# PILockbox_Zak_Jan_2016.net
KiCad netlist of a schematic drawn in EAGLE
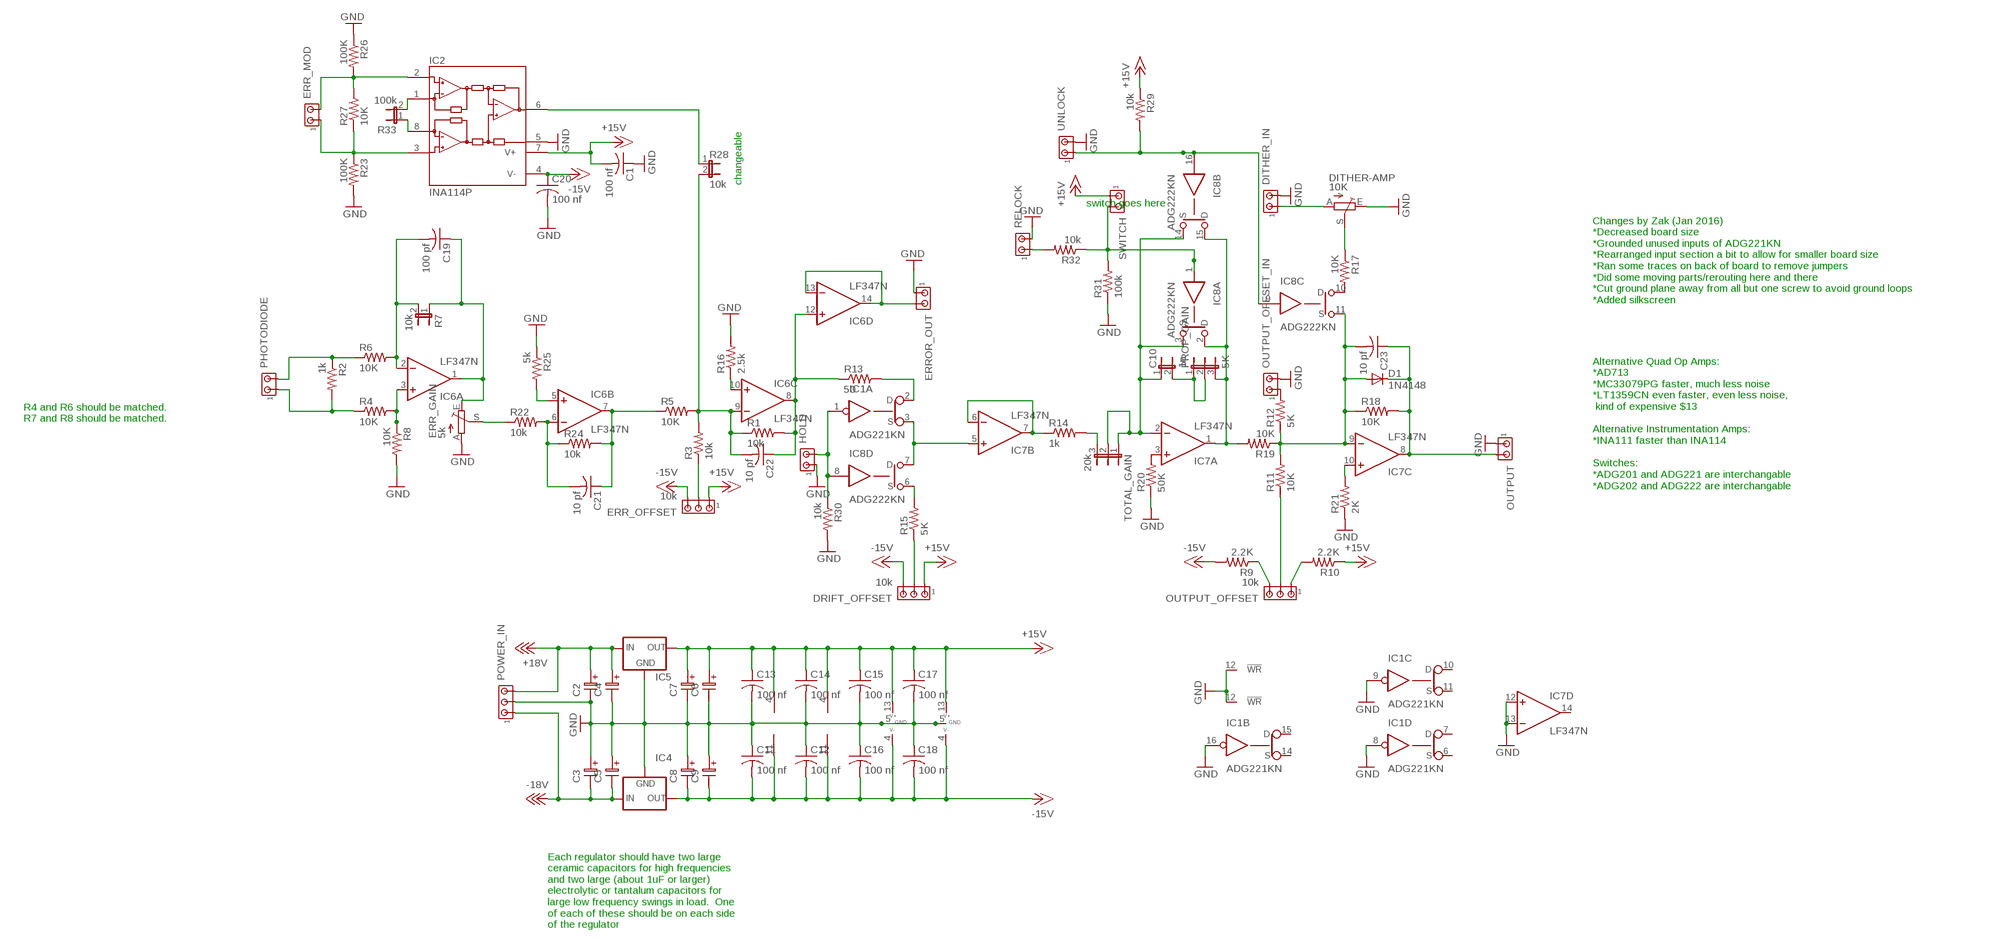
[diagram p0: schematic, sheet 1]

(export (version "E")
  (design (tool "Eeschema 10.0.6"))
  (components
    (comp (ref "C1")
      (value "100 nf")
      (footprint "eagle-import:C0805")
      (libsource (lib "eagle-import") (part "C-USC0805"))
    )
    (comp (ref "C2")
      (value "ELC-2,5")
      (footprint "eagle-import:ES-2,5")
      (libsource (lib "eagle-import") (part "ELC-2,5"))
    )
    (comp (ref "C3")
      (value "ELC-2,5")
      (footprint "eagle-import:ES-2,5")
      (libsource (lib "eagle-import") (part "ELC-2,5"))
    )
    (comp (ref "C4")
      (value "ELC-2,5")
      (footprint "eagle-import:ES-2,5")
      (libsource (lib "eagle-import") (part "ELC-2,5"))
    )
    (comp (ref "C5")
      (value "ELC-2,5")
      (footprint "eagle-import:ES-2,5")
      (libsource (lib "eagle-import") (part "ELC-2,5"))
    )
    (comp (ref "C6")
      (value "ELC-2,5")
      (footprint "eagle-import:ES-2,5")
      (libsource (lib "eagle-import") (part "ELC-2,5"))
    )
    (comp (ref "C7")
      (value "ELC-2,5")
      (footprint "eagle-import:ES-2,5")
      (libsource (lib "eagle-import") (part "ELC-2,5"))
    )
    (comp (ref "C8")
      (value "ELC-2,5")
      (footprint "eagle-import:ES-2,5")
      (libsource (lib "eagle-import") (part "ELC-2,5"))
    )
    (comp (ref "C9")
      (value "ELC-2,5")
      (footprint "eagle-import:ES-2,5")
      (libsource (lib "eagle-import") (part "ELC-2,5"))
    )
    (comp (ref "C10")
      (value "1n")
      (footprint "eagle-import:JP1")
      (libsource (lib "eagle-import") (part "JP1E"))
    )
    (comp (ref "C11")
      (value "100 nf")
      (footprint "eagle-import:C0805")
      (libsource (lib "eagle-import") (part "C-USC0805"))
    )
    (comp (ref "C12")
      (value "100 nf")
      (footprint "eagle-import:C0805")
      (libsource (lib "eagle-import") (part "C-USC0805"))
    )
    (comp (ref "C13")
      (value "100 nf")
      (footprint "eagle-import:C0805")
      (libsource (lib "eagle-import") (part "C-USC0805"))
    )
    (comp (ref "C14")
      (value "100 nf")
      (footprint "eagle-import:C0805")
      (libsource (lib "eagle-import") (part "C-USC0805"))
    )
    (comp (ref "C15")
      (value "100 nf")
      (footprint "eagle-import:C0805")
      (libsource (lib "eagle-import") (part "C-USC0805"))
    )
    (comp (ref "C16")
      (value "100 nf")
      (footprint "eagle-import:C0805")
      (libsource (lib "eagle-import") (part "C-USC0805"))
    )
    (comp (ref "C17")
      (value "100 nf")
      (footprint "eagle-import:C0805")
      (libsource (lib "eagle-import") (part "C-USC0805"))
    )
    (comp (ref "C18")
      (value "100 nf")
      (footprint "eagle-import:C0805")
      (libsource (lib "eagle-import") (part "C-USC0805"))
    )
    (comp (ref "C19")
      (value "100 pf")
      (footprint "eagle-import:C0805")
      (libsource (lib "eagle-import") (part "C-USC0805"))
    )
    (comp (ref "C20")
      (value "100 nf")
      (footprint "eagle-import:C0805")
      (libsource (lib "eagle-import") (part "C-USC0805"))
    )
    (comp (ref "C21")
      (value "10 pf")
      (footprint "eagle-import:C0805")
      (libsource (lib "eagle-import") (part "C-USC0805"))
    )
    (comp (ref "C22")
      (value "10 pf")
      (footprint "eagle-import:C0805")
      (libsource (lib "eagle-import") (part "C-USC0805"))
    )
    (comp (ref "C23")
      (value "10 pf")
      (footprint "eagle-import:C0805")
      (libsource (lib "eagle-import") (part "C-USC0805"))
    )
    (comp (ref "D1")
      (value "1N4148")
      (footprint "eagle-import:DO35-10")
      (libsource (lib "eagle-import") (part "1N4148"))
    )
    (comp (ref "DITHER-AMP")
      (value "10K")
      (footprint "eagle-import:RJ9W")
      (libsource (lib "eagle-import") (part "TRIM_EU-RJ9W"))
    )
    (comp (ref "DITHER_IN")
      (value "MTA02-100")
      (footprint "eagle-import:10X02MTA")
      (libsource (lib "eagle-import") (part "MTA02-100"))
    )
    (comp (ref "DRIFT_OFFSET")
      (value "10k")
      (footprint "eagle-import:10X03MTA")
      (libsource (lib "eagle-import") (part "MTA03-100"))
    )
    (comp (ref "ERROR_OUT")
      (value "MTA02-100")
      (footprint "eagle-import:10X02MTA")
      (libsource (lib "eagle-import") (part "MTA02-100"))
    )
    (comp (ref "ERR_GAIN")
      (value "5k")
      (footprint "eagle-import:RJ9W")
      (libsource (lib "eagle-import") (part "TRIM_EU-RJ9W"))
    )
    (comp (ref "ERR_MOD")
      (value "MTA02-100")
      (footprint "eagle-import:10X02MTA")
      (libsource (lib "eagle-import") (part "MTA02-100"))
    )
    (comp (ref "ERR_OFFSET")
      (value "10k")
      (footprint "eagle-import:10X03MTA")
      (libsource (lib "eagle-import") (part "MTA03-100"))
    )
    (comp (ref "HOLD")
      (value "MTA02-100")
      (footprint "eagle-import:10X02MTA")
      (libsource (lib "eagle-import") (part "MTA02-100"))
    )
    (comp (ref "IC1")
      (value "ADG221KN")
      (footprint "eagle-import:DIL16")
      (libsource (lib "eagle-import") (part "ADG221KN"))
    )
    (comp (ref "IC2")
      (value "INA114P")
      (footprint "eagle-import:DIL08")
      (libsource (lib "eagle-import") (part "INA114P"))
    )
    (comp (ref "IC4")
      (value "79XXL")
      (footprint "eagle-import:79XXL")
      (libsource (lib "eagle-import") (part "79XXL"))
    )
    (comp (ref "IC5")
      (value "78XXL")
      (footprint "eagle-import:78XXL")
      (libsource (lib "eagle-import") (part "78XXL"))
    )
    (comp (ref "IC6")
      (value "LF347N")
      (footprint "eagle-import:DIL14")
      (libsource (lib "eagle-import") (part "LF347N"))
    )
    (comp (ref "IC7")
      (value "LF347N")
      (footprint "eagle-import:DIL14")
      (libsource (lib "eagle-import") (part "LF347N"))
    )
    (comp (ref "IC8")
      (value "ADG222KN")
      (footprint "eagle-import:DIL16")
      (libsource (lib "eagle-import") (part "ADG222KN"))
    )
    (comp (ref "OUTPUT")
      (value "MTA02-100")
      (footprint "eagle-import:10X02MTA")
      (libsource (lib "eagle-import") (part "MTA02-100"))
    )
    (comp (ref "OUTPUT_OFFSET")
      (value "10k")
      (footprint "eagle-import:10X03MTA")
      (libsource (lib "eagle-import") (part "MTA03-100"))
    )
    (comp (ref "OUTPUT_OFFSET_IN")
      (value "MTA02-100")
      (footprint "eagle-import:10X02MTA")
      (libsource (lib "eagle-import") (part "MTA02-100"))
    )
    (comp (ref "PHOTODIODE")
      (value "MTA02-100")
      (footprint "eagle-import:10X02MTA")
      (libsource (lib "eagle-import") (part "MTA02-100"))
    )
    (comp (ref "POWER_IN")
      (value "MTA03-100")
      (footprint "eagle-import:10X03MTA")
      (libsource (lib "eagle-import") (part "MTA03-100"))
    )
    (comp (ref "PROP_GAIN")
      (value "5K")
      (footprint "eagle-import:JP2")
      (libsource (lib "eagle-import") (part "JP2E"))
    )
    (comp (ref "R1")
      (value "10k")
      (footprint "eagle-import:R1206")
      (libsource (lib "eagle-import") (part "R-US_R1206"))
    )
    (comp (ref "R2")
      (value "1k")
      (footprint "eagle-import:R1206")
      (libsource (lib "eagle-import") (part "R-US_R1206"))
    )
    (comp (ref "R3")
      (value "10k")
      (footprint "eagle-import:R1206")
      (libsource (lib "eagle-import") (part "R-US_R1206"))
    )
    (comp (ref "R4")
      (value "10K")
      (footprint "eagle-import:R1206")
      (libsource (lib "eagle-import") (part "R-US_R1206"))
    )
    (comp (ref "R5")
      (value "10K")
      (footprint "eagle-import:R1206")
      (libsource (lib "eagle-import") (part "R-US_R1206"))
    )
    (comp (ref "R6")
      (value "10K")
      (footprint "eagle-import:R1206")
      (libsource (lib "eagle-import") (part "R-US_R1206"))
    )
    (comp (ref "R7")
      (value "10k")
      (footprint "eagle-import:JP1")
      (libsource (lib "eagle-import") (part "JP1E"))
    )
    (comp (ref "R8")
      (value "10K")
      (footprint "eagle-import:R1206")
      (libsource (lib "eagle-import") (part "R-US_R1206"))
    )
    (comp (ref "R9")
      (value "2.2K")
      (footprint "eagle-import:R1206")
      (libsource (lib "eagle-import") (part "R-US_R1206"))
    )
    (comp (ref "R10")
      (value "2.2K")
      (footprint "eagle-import:R1206")
      (libsource (lib "eagle-import") (part "R-US_R1206"))
    )
    (comp (ref "R11")
      (value "10K")
      (footprint "eagle-import:R1206")
      (libsource (lib "eagle-import") (part "R-US_R1206"))
    )
    (comp (ref "R12")
      (value "5K")
      (footprint "eagle-import:R1206")
      (libsource (lib "eagle-import") (part "R-US_R1206"))
    )
    (comp (ref "R13")
      (value "50")
      (footprint "eagle-import:R1206")
      (libsource (lib "eagle-import") (part "R-US_R1206"))
    )
    (comp (ref "R14")
      (value "1k")
      (footprint "eagle-import:R1206")
      (libsource (lib "eagle-import") (part "R-US_R1206"))
    )
    (comp (ref "R15")
      (value "5K")
      (footprint "eagle-import:R1206")
      (libsource (lib "eagle-import") (part "R-US_R1206"))
    )
    (comp (ref "R16")
      (value "2.5k")
      (footprint "eagle-import:R1206")
      (libsource (lib "eagle-import") (part "R-US_R1206"))
    )
    (comp (ref "R17")
      (value "10K")
      (footprint "eagle-import:R1206")
      (libsource (lib "eagle-import") (part "R-US_R1206"))
    )
    (comp (ref "R18")
      (value "10K")
      (footprint "eagle-import:R1206")
      (libsource (lib "eagle-import") (part "R-US_R1206"))
    )
    (comp (ref "R19")
      (value "10K")
      (footprint "eagle-import:R1206")
      (libsource (lib "eagle-import") (part "R-US_R1206"))
    )
    (comp (ref "R20")
      (value "50K")
      (footprint "eagle-import:R1206")
      (libsource (lib "eagle-import") (part "R-US_R1206"))
    )
    (comp (ref "R21")
      (value "2K")
      (footprint "eagle-import:R1206")
      (libsource (lib "eagle-import") (part "R-US_R1206"))
    )
    (comp (ref "R22")
      (value "10k")
      (footprint "eagle-import:R1206")
      (libsource (lib "eagle-import") (part "R-US_R1206"))
    )
    (comp (ref "R23")
      (value "100K")
      (footprint "eagle-import:R1206")
      (libsource (lib "eagle-import") (part "R-US_R1206"))
    )
    (comp (ref "R24")
      (value "10k")
      (footprint "eagle-import:R1206")
      (libsource (lib "eagle-import") (part "R-US_R1206"))
    )
    (comp (ref "R25")
      (value "5k")
      (footprint "eagle-import:R1206")
      (libsource (lib "eagle-import") (part "R-US_R1206"))
    )
    (comp (ref "R26")
      (value "100K")
      (footprint "eagle-import:R1206")
      (libsource (lib "eagle-import") (part "R-US_R1206"))
    )
    (comp (ref "R27")
      (value "10K")
      (footprint "eagle-import:R1206")
      (libsource (lib "eagle-import") (part "R-US_R1206"))
    )
    (comp (ref "R28")
      (value "10k")
      (footprint "eagle-import:JP1")
      (libsource (lib "eagle-import") (part "JP1E"))
    )
    (comp (ref "R29")
      (value "10k")
      (footprint "eagle-import:R1206")
      (libsource (lib "eagle-import") (part "R-US_R1206"))
    )
    (comp (ref "R30")
      (value "10k")
      (footprint "eagle-import:R1206")
      (libsource (lib "eagle-import") (part "R-US_R1206"))
    )
    (comp (ref "R31")
      (value "100k")
      (footprint "eagle-import:R1206")
      (libsource (lib "eagle-import") (part "R-US_R1206"))
    )
    (comp (ref "R32")
      (value "10k")
      (footprint "eagle-import:R1206")
      (libsource (lib "eagle-import") (part "R-US_R1206"))
    )
    (comp (ref "R33")
      (value "100k")
      (footprint "eagle-import:JP1")
      (libsource (lib "eagle-import") (part "JP1E"))
    )
    (comp (ref "RELOCK")
      (value "MTA02-100")
      (footprint "eagle-import:10X02MTA")
      (libsource (lib "eagle-import") (part "MTA02-100"))
    )
    (comp (ref "SWITCH")
      (value "MTA02-100")
      (footprint "eagle-import:10X02MTA")
      (libsource (lib "eagle-import") (part "MTA02-100"))
    )
    (comp (ref "TOTAL_GAIN")
      (value "20k")
      (footprint "eagle-import:JP2")
      (libsource (lib "eagle-import") (part "JP2E"))
    )
    (comp (ref "UNLOCK")
      (value "MTA02-100")
      (footprint "eagle-import:10X02MTA")
      (libsource (lib "eagle-import") (part "MTA02-100"))
    )
  )
  (nets
    (net (code "1") (name "+15V") (class "Default")
      (node (ref "C1") (pin "2") (pinfunction "2_2") (pintype "passive"))
      (node (ref "C13") (pin "1") (pinfunction "1_1") (pintype "passive"))
      (node (ref "C14") (pin "1") (pinfunction "1_1") (pintype "passive"))
      (node (ref "C15") (pin "1") (pinfunction "1_1") (pintype "passive"))
      (node (ref "C17") (pin "1") (pinfunction "1_1") (pintype "passive"))
      (node (ref "C6") (pin "1") (pinfunction "1_1") (pintype "passive"))
      (node (ref "C7") (pin "1") (pinfunction "1_1") (pintype "passive"))
      (node (ref "DRIFT_OFFSET") (pin "1") (pinfunction "1_1") (pintype "passive"))
      (node (ref "ERR_OFFSET") (pin "1") (pinfunction "1_1") (pintype "passive"))
      (node (ref "IC1") (pin "13") (pinfunction "V+_13") (pintype "power_in"))
      (node (ref "IC2") (pin "7") (pinfunction "V+_7") (pintype "power_in"))
      (node (ref "IC5") (pin "OUT") (pinfunction "OUT_OUT") (pintype "passive"))
      (node (ref "IC6") (pin "4") (pinfunction "V+_4") (pintype "power_in"))
      (node (ref "IC7") (pin "4") (pinfunction "V+_4") (pintype "power_in"))
      (node (ref "IC8") (pin "13") (pinfunction "V+_13") (pintype "power_in"))
      (node (ref "R10") (pin "1") (pinfunction "1_1") (pintype "passive"))
      (node (ref "R29") (pin "1") (pinfunction "1_1") (pintype "passive"))
      (node (ref "SWITCH") (pin "1") (pinfunction "1_1") (pintype "passive"))
    )
    (net (code "2") (name "+18V") (class "Default")
      (node (ref "C2") (pin "1") (pinfunction "1_1") (pintype "passive"))
      (node (ref "C4") (pin "1") (pinfunction "1_1") (pintype "passive"))
      (node (ref "IC5") (pin "IN") (pinfunction "IN_IN") (pintype "input"))
      (node (ref "POWER_IN") (pin "3") (pinfunction "3_3") (pintype "passive"))
    )
    (net (code "3") (name "-15V") (class "Default")
      (node (ref "C11") (pin "2") (pinfunction "2_2") (pintype "passive"))
      (node (ref "C12") (pin "2") (pinfunction "2_2") (pintype "passive"))
      (node (ref "C16") (pin "2") (pinfunction "2_2") (pintype "passive"))
      (node (ref "C18") (pin "2") (pinfunction "2_2") (pintype "passive"))
      (node (ref "C20") (pin "1") (pinfunction "1_1") (pintype "passive"))
      (node (ref "C8") (pin "2") (pinfunction "2_2") (pintype "passive"))
      (node (ref "C9") (pin "2") (pinfunction "2_2") (pintype "passive"))
      (node (ref "DRIFT_OFFSET") (pin "3") (pinfunction "3_3") (pintype "passive"))
      (node (ref "ERR_OFFSET") (pin "3") (pinfunction "3_3") (pintype "passive"))
      (node (ref "IC1") (pin "4") (pinfunction "V-_4") (pintype "power_in"))
      (node (ref "IC2") (pin "4") (pinfunction "V-_4") (pintype "power_in"))
      (node (ref "IC4") (pin "OUT") (pinfunction "OUT_OUT") (pintype "passive"))
      (node (ref "IC6") (pin "11") (pinfunction "V-_11") (pintype "power_in"))
      (node (ref "IC7") (pin "11") (pinfunction "V-_11") (pintype "power_in"))
      (node (ref "IC8") (pin "4") (pinfunction "V-_4") (pintype "power_in"))
      (node (ref "R9") (pin "2") (pinfunction "2_2") (pintype "passive"))
    )
    (net (code "4") (name "-18V") (class "Default")
      (node (ref "C3") (pin "2") (pinfunction "2_2") (pintype "passive"))
      (node (ref "C5") (pin "2") (pinfunction "2_2") (pintype "passive"))
      (node (ref "IC4") (pin "IN") (pinfunction "IN_IN") (pintype "input"))
      (node (ref "POWER_IN") (pin "1") (pinfunction "1_1") (pintype "passive"))
    )
    (net (code "5") (name "GND") (class "Default")
      (node (ref "C1") (pin "1") (pinfunction "1_1") (pintype "passive"))
      (node (ref "C11") (pin "1") (pinfunction "1_1") (pintype "passive"))
      (node (ref "C12") (pin "1") (pinfunction "1_1") (pintype "passive"))
      (node (ref "C13") (pin "2") (pinfunction "2_2") (pintype "passive"))
      (node (ref "C14") (pin "2") (pinfunction "2_2") (pintype "passive"))
      (node (ref "C15") (pin "2") (pinfunction "2_2") (pintype "passive"))
      (node (ref "C16") (pin "1") (pinfunction "1_1") (pintype "passive"))
      (node (ref "C17") (pin "2") (pinfunction "2_2") (pintype "passive"))
      (node (ref "C18") (pin "1") (pinfunction "1_1") (pintype "passive"))
      (node (ref "C2") (pin "2") (pinfunction "2_2") (pintype "passive"))
      (node (ref "C20") (pin "2") (pinfunction "2_2") (pintype "passive"))
      (node (ref "C3") (pin "1") (pinfunction "1_1") (pintype "passive"))
      (node (ref "C4") (pin "2") (pinfunction "2_2") (pintype "passive"))
      (node (ref "C5") (pin "1") (pinfunction "1_1") (pintype "passive"))
      (node (ref "C6") (pin "2") (pinfunction "2_2") (pintype "passive"))
      (node (ref "C7") (pin "2") (pinfunction "2_2") (pintype "passive"))
      (node (ref "C8") (pin "1") (pinfunction "1_1") (pintype "passive"))
      (node (ref "C9") (pin "1") (pinfunction "1_1") (pintype "passive"))
      (node (ref "DITHER-AMP") (pin "E") (pinfunction "E_E") (pintype "passive"))
      (node (ref "DITHER_IN") (pin "2") (pinfunction "2_2") (pintype "passive"))
      (node (ref "ERROR_OUT") (pin "1") (pinfunction "1_1") (pintype "passive"))
      (node (ref "ERR_GAIN") (pin "A") (pinfunction "A_A") (pintype "passive"))
      (node (ref "HOLD") (pin "1") (pinfunction "1_1") (pintype "passive"))
      (node (ref "IC1") (pin "12") (pinfunction "~{WR}_12") (pintype "input"))
      (node (ref "IC1") (pin "16") (pinfunction "IN_16") (pintype "input"))
      (node (ref "IC1") (pin "5") (pinfunction "GND_5") (pintype "power_in"))
      (node (ref "IC1") (pin "8") (pinfunction "IN_8") (pintype "input"))
      (node (ref "IC1") (pin "9") (pinfunction "IN_9") (pintype "input"))
      (node (ref "IC2") (pin "5") (pinfunction "REF_5") (pintype "passive"))
      (node (ref "IC4") (pin "GND") (pinfunction "GND_GND") (pintype "input"))
      (node (ref "IC5") (pin "GND") (pinfunction "GND_GND") (pintype "input"))
      (node (ref "IC7") (pin "12") (pinfunction "+IN_12") (pintype "input"))
      (node (ref "IC7") (pin "13") (pinfunction "-IN_13") (pintype "input"))
      (node (ref "IC8") (pin "12") (pinfunction "~{WR}_12") (pintype "input"))
      (node (ref "IC8") (pin "5") (pinfunction "GND_5") (pintype "power_in"))
      (node (ref "OUTPUT") (pin "1") (pinfunction "1_1") (pintype "passive"))
      (node (ref "OUTPUT_OFFSET_IN") (pin "2") (pinfunction "2_2") (pintype "passive"))
      (node (ref "POWER_IN") (pin "2") (pinfunction "2_2") (pintype "passive"))
      (node (ref "R16") (pin "2") (pinfunction "2_2") (pintype "passive"))
      (node (ref "R20") (pin "1") (pinfunction "1_1") (pintype "passive"))
      (node (ref "R21") (pin "1") (pinfunction "1_1") (pintype "passive"))
      (node (ref "R23") (pin "2") (pinfunction "2_2") (pintype "passive"))
      (node (ref "R25") (pin "1") (pinfunction "1_1") (pintype "passive"))
      (node (ref "R26") (pin "1") (pinfunction "1_1") (pintype "passive"))
      (node (ref "R30") (pin "2") (pinfunction "2_2") (pintype "passive"))
      (node (ref "R31") (pin "1") (pinfunction "1_1") (pintype "passive"))
      (node (ref "R8") (pin "2") (pinfunction "2_2") (pintype "passive"))
      (node (ref "RELOCK") (pin "2") (pinfunction "2_2") (pintype "passive"))
      (node (ref "UNLOCK") (pin "2") (pinfunction "2_2") (pintype "passive"))
    )
    (net (code "6") (name "Net-(C10-Pad2)") (class "Default")
      (node (ref "C10") (pin "2") (pinfunction "2_2") (pintype "passive"))
      (node (ref "PROP_GAIN") (pin "1") (pinfunction "1_1") (pintype "passive"))
      (node (ref "PROP_GAIN") (pin "2") (pinfunction "2_2") (pintype "passive"))
    )
    (net (code "7") (name "Net-(DITHER-AMP-PadA)") (class "Default")
      (node (ref "DITHER-AMP") (pin "A") (pinfunction "A_A") (pintype "passive"))
      (node (ref "DITHER_IN") (pin "1") (pinfunction "1_1") (pintype "passive"))
    )
    (net (code "8") (name "Net-(DITHER-AMP-PadS)") (class "Default")
      (node (ref "DITHER-AMP") (pin "S") (pinfunction "S_S") (pintype "passive"))
      (node (ref "R17") (pin "1") (pinfunction "1_1") (pintype "passive"))
    )
    (net (code "9") (name "Net-(DRIFT_OFFSET-Pad2)") (class "Default")
      (node (ref "DRIFT_OFFSET") (pin "2") (pinfunction "2_2") (pintype "passive"))
      (node (ref "R15") (pin "1") (pinfunction "1_1") (pintype "passive"))
    )
    (net (code "10") (name "Net-(ERR_GAIN-PadS)") (class "Default")
      (node (ref "ERR_GAIN") (pin "S") (pinfunction "S_S") (pintype "passive"))
      (node (ref "R22") (pin "1") (pinfunction "1_1") (pintype "passive"))
    )
    (net (code "11") (name "Net-(ERR_OFFSET-Pad2)") (class "Default")
      (node (ref "ERR_OFFSET") (pin "2") (pinfunction "2_2") (pintype "passive"))
      (node (ref "R3") (pin "1") (pinfunction "1_1") (pintype "passive"))
    )
    (net (code "12") (name "Net-(IC1A-D)") (class "Default")
      (node (ref "IC1") (pin "2") (pinfunction "D_2") (pintype "bidirectional"))
      (node (ref "R13") (pin "2") (pinfunction "2_2") (pintype "passive"))
    )
    (net (code "13") (name "Net-(IC1A-IN)") (class "Default")
      (node (ref "HOLD") (pin "2") (pinfunction "2_2") (pintype "passive"))
      (node (ref "IC1") (pin "1") (pinfunction "IN_1") (pintype "input"))
      (node (ref "IC8") (pin "8") (pinfunction "IN_8") (pintype "input"))
      (node (ref "R30") (pin "1") (pinfunction "1_1") (pintype "passive"))
    )
    (net (code "14") (name "Net-(IC1A-S)") (class "Default")
      (node (ref "IC1") (pin "3") (pinfunction "S_3") (pintype "bidirectional"))
      (node (ref "IC7") (pin "5") (pinfunction "+IN_5") (pintype "input"))
      (node (ref "IC8") (pin "7") (pinfunction "D_7") (pintype "bidirectional"))
    )
    (net (code "15") (name "Net-(IC2-+IN)") (class "Default")
      (node (ref "ERR_MOD") (pin "1") (pinfunction "1_1") (pintype "passive"))
      (node (ref "IC2") (pin "3") (pinfunction "+IN_3") (pintype "input"))
      (node (ref "R23") (pin "1") (pinfunction "1_1") (pintype "passive"))
      (node (ref "R27") (pin "1") (pinfunction "1_1") (pintype "passive"))
    )
    (net (code "16") (name "Net-(IC2--IN)") (class "Default")
      (node (ref "ERR_MOD") (pin "2") (pinfunction "2_2") (pintype "passive"))
      (node (ref "IC2") (pin "2") (pinfunction "-IN_2") (pintype "input"))
      (node (ref "R26") (pin "2") (pinfunction "2_2") (pintype "passive"))
      (node (ref "R27") (pin "2") (pinfunction "2_2") (pintype "passive"))
    )
    (net (code "17") (name "Net-(IC2-OUT)") (class "Default")
      (node (ref "IC2") (pin "6") (pinfunction "OUT_6") (pintype "output"))
      (node (ref "R28") (pin "1") (pinfunction "1_1") (pintype "passive"))
    )
    (net (code "18") (name "Net-(IC2-RG-Pad1)") (class "Default")
      (node (ref "IC2") (pin "1") (pinfunction "RG_1") (pintype "passive"))
      (node (ref "R33") (pin "2") (pinfunction "2_2") (pintype "passive"))
    )
    (net (code "19") (name "Net-(IC2-RG-Pad8)") (class "Default")
      (node (ref "IC2") (pin "8") (pinfunction "RG_8") (pintype "passive"))
      (node (ref "R33") (pin "1") (pinfunction "1_1") (pintype "passive"))
    )
    (net (code "20") (name "Net-(IC6A-+IN)") (class "Default")
      (node (ref "IC6") (pin "3") (pinfunction "+IN_3") (pintype "input"))
      (node (ref "R4") (pin "2") (pinfunction "2_2") (pintype "passive"))
      (node (ref "R8") (pin "1") (pinfunction "1_1") (pintype "passive"))
    )
    (net (code "21") (name "Net-(IC6A--IN)") (class "Default")
      (node (ref "C19") (pin "2") (pinfunction "2_2") (pintype "passive"))
      (node (ref "IC6") (pin "2") (pinfunction "-IN_2") (pintype "input"))
      (node (ref "R6") (pin "2") (pinfunction "2_2") (pintype "passive"))
      (node (ref "R7") (pin "2") (pinfunction "2_2") (pintype "passive"))
    )
    (net (code "22") (name "Net-(IC6A-OUT)") (class "Default")
      (node (ref "C19") (pin "1") (pinfunction "1_1") (pintype "passive"))
      (node (ref "ERR_GAIN") (pin "E") (pinfunction "E_E") (pintype "passive"))
      (node (ref "IC6") (pin "1") (pinfunction "OUT_1") (pintype "output"))
      (node (ref "R7") (pin "1") (pinfunction "1_1") (pintype "passive"))
    )
    (net (code "23") (name "Net-(IC6B-+IN)") (class "Default")
      (node (ref "IC6") (pin "5") (pinfunction "+IN_5") (pintype "input"))
      (node (ref "R25") (pin "2") (pinfunction "2_2") (pintype "passive"))
    )
    (net (code "24") (name "Net-(IC6B--IN)") (class "Default")
      (node (ref "C21") (pin "2") (pinfunction "2_2") (pintype "passive"))
      (node (ref "IC6") (pin "6") (pinfunction "-IN_6") (pintype "input"))
      (node (ref "R22") (pin "2") (pinfunction "2_2") (pintype "passive"))
      (node (ref "R24") (pin "1") (pinfunction "1_1") (pintype "passive"))
    )
    (net (code "25") (name "Net-(IC6B-OUT)") (class "Default")
      (node (ref "C21") (pin "1") (pinfunction "1_1") (pintype "passive"))
      (node (ref "IC6") (pin "7") (pinfunction "OUT_7") (pintype "output"))
      (node (ref "R24") (pin "2") (pinfunction "2_2") (pintype "passive"))
      (node (ref "R5") (pin "1") (pinfunction "1_1") (pintype "passive"))
    )
    (net (code "26") (name "Net-(IC6C-+IN)") (class "Default")
      (node (ref "IC6") (pin "10") (pinfunction "+IN_10") (pintype "input"))
      (node (ref "R16") (pin "1") (pinfunction "1_1") (pintype "passive"))
    )
    (net (code "27") (name "Net-(IC6C--IN)") (class "Default")
      (node (ref "C22") (pin "2") (pinfunction "2_2") (pintype "passive"))
      (node (ref "IC6") (pin "9") (pinfunction "-IN_9") (pintype "input"))
      (node (ref "R1") (pin "1") (pinfunction "1_1") (pintype "passive"))
      (node (ref "R28") (pin "2") (pinfunction "2_2") (pintype "passive"))
      (node (ref "R3") (pin "2") (pinfunction "2_2") (pintype "passive"))
      (node (ref "R5") (pin "2") (pinfunction "2_2") (pintype "passive"))
    )
    (net (code "28") (name "Net-(IC6C-OUT)") (class "Default")
      (node (ref "C22") (pin "1") (pinfunction "1_1") (pintype "passive"))
      (node (ref "IC6") (pin "12") (pinfunction "+IN_12") (pintype "input"))
      (node (ref "IC6") (pin "8") (pinfunction "OUT_8") (pintype "output"))
      (node (ref "R1") (pin "2") (pinfunction "2_2") (pintype "passive"))
      (node (ref "R13") (pin "1") (pinfunction "1_1") (pintype "passive"))
    )
    (net (code "29") (name "Net-(IC6D--IN)") (class "Default")
      (node (ref "ERROR_OUT") (pin "2") (pinfunction "2_2") (pintype "passive"))
      (node (ref "IC6") (pin "13") (pinfunction "-IN_13") (pintype "input"))
      (node (ref "IC6") (pin "14") (pinfunction "OUT_14") (pintype "output"))
    )
    (net (code "30") (name "Net-(IC7A-+IN)") (class "Default")
      (node (ref "IC7") (pin "3") (pinfunction "+IN_3") (pintype "input"))
      (node (ref "R20") (pin "2") (pinfunction "2_2") (pintype "passive"))
    )
    (net (code "31") (name "Net-(IC7A--IN)") (class "Default")
      (node (ref "C10") (pin "1") (pinfunction "1_1") (pintype "passive"))
      (node (ref "IC7") (pin "2") (pinfunction "-IN_2") (pintype "input"))
      (node (ref "IC8") (pin "14") (pinfunction "S_14") (pintype "bidirectional"))
      (node (ref "IC8") (pin "3") (pinfunction "S_3") (pintype "bidirectional"))
      (node (ref "TOTAL_GAIN") (pin "1") (pinfunction "1_1") (pintype "passive"))
      (node (ref "TOTAL_GAIN") (pin "2") (pinfunction "2_2") (pintype "passive"))
    )
    (net (code "32") (name "Net-(IC7A-OUT)") (class "Default")
      (node (ref "IC7") (pin "1") (pinfunction "OUT_1") (pintype "output"))
      (node (ref "IC8") (pin "15") (pinfunction "D_15") (pintype "bidirectional"))
      (node (ref "IC8") (pin "2") (pinfunction "D_2") (pintype "bidirectional"))
      (node (ref "PROP_GAIN") (pin "3") (pinfunction "3_3") (pintype "passive"))
      (node (ref "R19") (pin "2") (pinfunction "2_2") (pintype "passive"))
    )
    (net (code "33") (name "Net-(IC7B--IN)") (class "Default")
      (node (ref "IC7") (pin "6") (pinfunction "-IN_6") (pintype "input"))
      (node (ref "IC7") (pin "7") (pinfunction "OUT_7") (pintype "output"))
      (node (ref "R14") (pin "1") (pinfunction "1_1") (pintype "passive"))
    )
    (net (code "34") (name "Net-(IC7C-+IN)") (class "Default")
      (node (ref "IC7") (pin "10") (pinfunction "+IN_10") (pintype "input"))
      (node (ref "R21") (pin "2") (pinfunction "2_2") (pintype "passive"))
    )
    (net (code "35") (name "Net-(IC7C--IN)") (class "Default")
      (node (ref "C23") (pin "2") (pinfunction "2_2") (pintype "passive"))
      (node (ref "D1") (pin "A") (pinfunction "A_A") (pintype "passive"))
      (node (ref "IC7") (pin "9") (pinfunction "-IN_9") (pintype "input"))
      (node (ref "IC8") (pin "11") (pinfunction "S_11") (pintype "bidirectional"))
      (node (ref "R11") (pin "2") (pinfunction "2_2") (pintype "passive"))
      (node (ref "R12") (pin "1") (pinfunction "1_1") (pintype "passive"))
      (node (ref "R18") (pin "1") (pinfunction "1_1") (pintype "passive"))
      (node (ref "R19") (pin "1") (pinfunction "1_1") (pintype "passive"))
    )
    (net (code "36") (name "Net-(IC7C-OUT)") (class "Default")
      (node (ref "C23") (pin "1") (pinfunction "1_1") (pintype "passive"))
      (node (ref "D1") (pin "C") (pinfunction "C_C") (pintype "passive"))
      (node (ref "IC7") (pin "8") (pinfunction "OUT_8") (pintype "output"))
      (node (ref "OUTPUT") (pin "2") (pinfunction "2_2") (pintype "passive"))
      (node (ref "R18") (pin "2") (pinfunction "2_2") (pintype "passive"))
    )
    (net (code "37") (name "Net-(IC8A-IN)") (class "Default")
      (node (ref "IC8") (pin "1") (pinfunction "IN_1") (pintype "input"))
      (node (ref "R31") (pin "2") (pinfunction "2_2") (pintype "passive"))
      (node (ref "R32") (pin "1") (pinfunction "1_1") (pintype "passive"))
      (node (ref "SWITCH") (pin "2") (pinfunction "2_2") (pintype "passive"))
    )
    (net (code "38") (name "Net-(IC8B-IN)") (class "Default")
      (node (ref "IC8") (pin "16") (pinfunction "IN_16") (pintype "input"))
      (node (ref "IC8") (pin "9") (pinfunction "IN_9") (pintype "input"))
      (node (ref "R29") (pin "2") (pinfunction "2_2") (pintype "passive"))
      (node (ref "UNLOCK") (pin "1") (pinfunction "1_1") (pintype "passive"))
    )
    (net (code "39") (name "Net-(IC8C-D)") (class "Default")
      (node (ref "IC8") (pin "10") (pinfunction "D_10") (pintype "bidirectional"))
      (node (ref "R17") (pin "2") (pinfunction "2_2") (pintype "passive"))
    )
    (net (code "40") (name "Net-(IC8D-S)") (class "Default")
      (node (ref "IC8") (pin "6") (pinfunction "S_6") (pintype "bidirectional"))
      (node (ref "R15") (pin "2") (pinfunction "2_2") (pintype "passive"))
    )
    (net (code "41") (name "Net-(OUTPUT_OFFSET-Pad1)") (class "Default")
      (node (ref "OUTPUT_OFFSET") (pin "1") (pinfunction "1_1") (pintype "passive"))
      (node (ref "R10") (pin "2") (pinfunction "2_2") (pintype "passive"))
    )
    (net (code "42") (name "Net-(OUTPUT_OFFSET-Pad2)") (class "Default")
      (node (ref "OUTPUT_OFFSET") (pin "2") (pinfunction "2_2") (pintype "passive"))
      (node (ref "R11") (pin "1") (pinfunction "1_1") (pintype "passive"))
    )
    (net (code "43") (name "Net-(OUTPUT_OFFSET-Pad3)") (class "Default")
      (node (ref "OUTPUT_OFFSET") (pin "3") (pinfunction "3_3") (pintype "passive"))
      (node (ref "R9") (pin "1") (pinfunction "1_1") (pintype "passive"))
    )
    (net (code "44") (name "Net-(OUTPUT_OFFSET_IN-Pad1)") (class "Default")
      (node (ref "OUTPUT_OFFSET_IN") (pin "1") (pinfunction "1_1") (pintype "passive"))
      (node (ref "R12") (pin "2") (pinfunction "2_2") (pintype "passive"))
    )
    (net (code "45") (name "Net-(PHOTODIODE-Pad1)") (class "Default")
      (node (ref "PHOTODIODE") (pin "1") (pinfunction "1_1") (pintype "passive"))
      (node (ref "R2") (pin "2") (pinfunction "2_2") (pintype "passive"))
      (node (ref "R4") (pin "1") (pinfunction "1_1") (pintype "passive"))
    )
    (net (code "46") (name "Net-(PHOTODIODE-Pad2)") (class "Default")
      (node (ref "PHOTODIODE") (pin "2") (pinfunction "2_2") (pintype "passive"))
      (node (ref "R2") (pin "1") (pinfunction "1_1") (pintype "passive"))
      (node (ref "R6") (pin "1") (pinfunction "1_1") (pintype "passive"))
    )
    (net (code "47") (name "Net-(R14-Pad2)") (class "Default")
      (node (ref "R14") (pin "2") (pinfunction "2_2") (pintype "passive"))
      (node (ref "TOTAL_GAIN") (pin "3") (pinfunction "3_3") (pintype "passive"))
    )
    (net (code "48") (name "Net-(R32-Pad2)") (class "Default")
      (node (ref "R32") (pin "2") (pinfunction "2_2") (pintype "passive"))
      (node (ref "RELOCK") (pin "1") (pinfunction "1_1") (pintype "passive"))
    )
    (net (code "49") (name "unconnected-(IC1B-D-Pad15)") (class "Default")
      (node (ref "IC1") (pin "15") (pinfunction "D_15") (pintype "bidirectional"))
    )
    (net (code "50") (name "unconnected-(IC1B-S-Pad14)") (class "Default")
      (node (ref "IC1") (pin "14") (pinfunction "S_14") (pintype "bidirectional"))
    )
    (net (code "51") (name "unconnected-(IC1C-D-Pad10)") (class "Default")
      (node (ref "IC1") (pin "10") (pinfunction "D_10") (pintype "bidirectional"))
    )
    (net (code "52") (name "unconnected-(IC1C-S-Pad11)") (class "Default")
      (node (ref "IC1") (pin "11") (pinfunction "S_11") (pintype "bidirectional"))
    )
    (net (code "53") (name "unconnected-(IC1D-D-Pad7)") (class "Default")
      (node (ref "IC1") (pin "7") (pinfunction "D_7") (pintype "bidirectional"))
    )
    (net (code "54") (name "unconnected-(IC1D-S-Pad6)") (class "Default")
      (node (ref "IC1") (pin "6") (pinfunction "S_6") (pintype "bidirectional"))
    )
    (net (code "55") (name "unconnected-(IC7D-OUT-Pad14)") (class "Default")
      (node (ref "IC7") (pin "14") (pinfunction "OUT_14") (pintype "output"))
    )
  )
)
